# MIDIInterface.net
KiCad netlist of a schematic drawn in Altium Designer
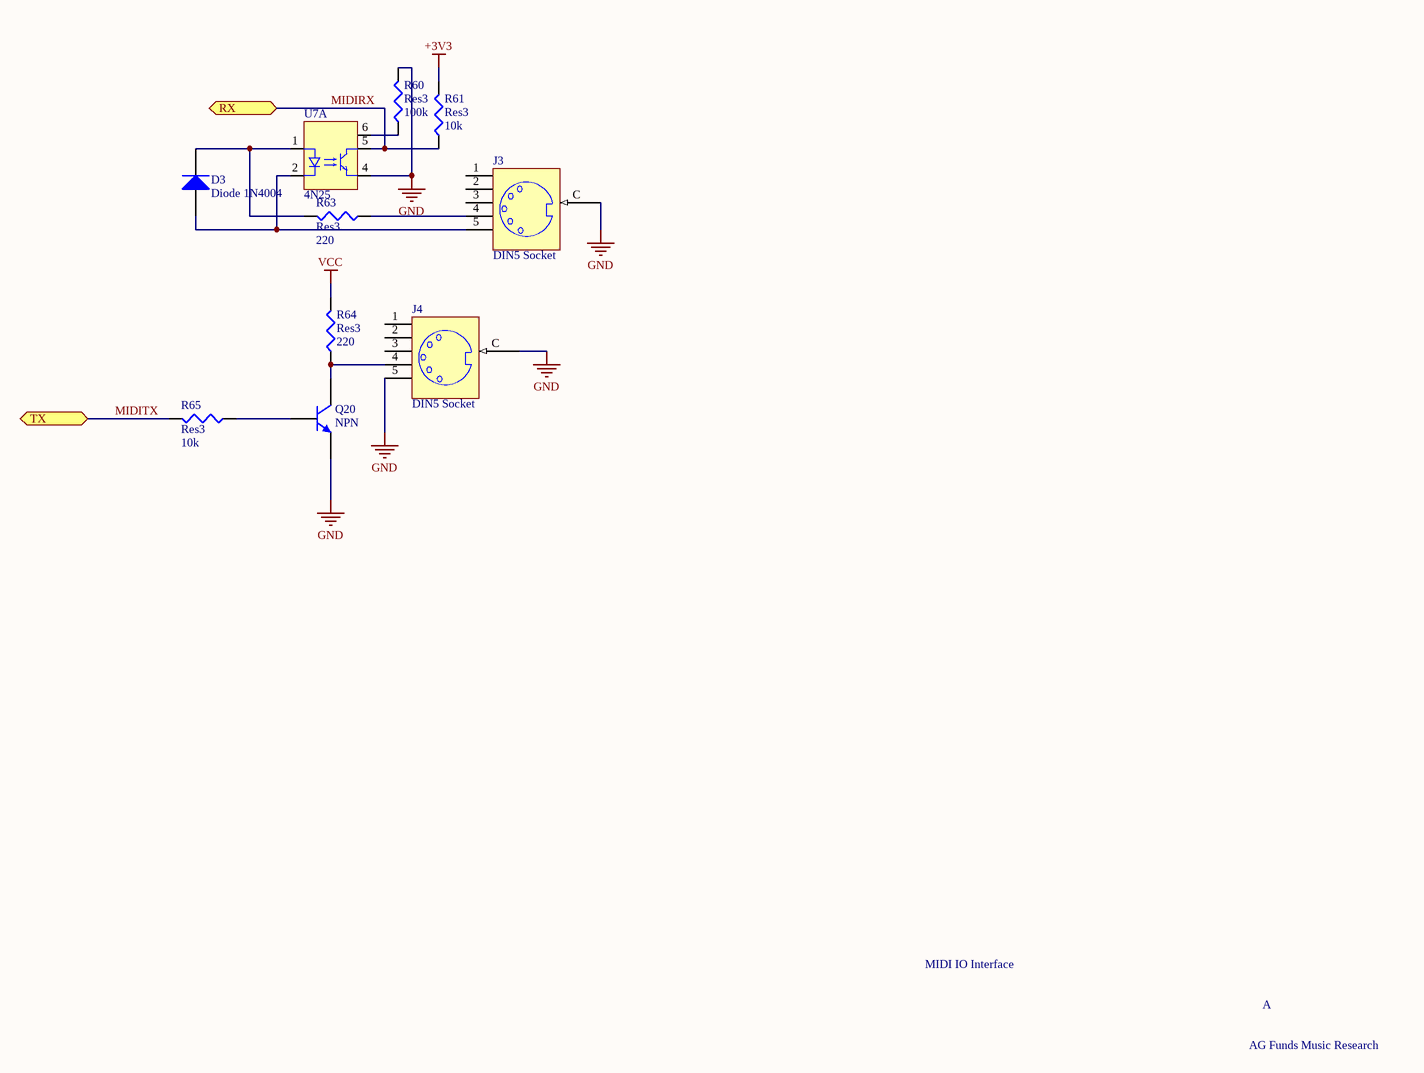
[diagram p0: MIDIInterface.SchDoc]

(export (version "E")
  (design (tool "Eeschema 10.0.6"))
  (components
    (comp (ref "D3")
      (value "Diode 1N4004")
      (footprint "DO-41")
      (description "1 Amp General Purpose Rectifier")
      (fields (field (name "PUBLISHER") "Altium Limited"))
      (libsource (lib "Miscellaneous Devices") (part "Diode 1N4004"))
    )
    (comp (ref "J3")
      (value "DIN5 Socket")
      (footprint "RGBLED:DIN-5")
      (description "CUI Inc. SDS-50J DIN5 PCB Mount Socket")
      (fields (field (name "PUBLISHER") "Altium Limited"))
      (libsource (lib "MIDIPiano_7") (part "DIN5"))
    )
    (comp (ref "J4")
      (value "DIN5 Socket")
      (footprint "RGBLED:DIN-5")
      (description "CUI Inc. SDS-50J DIN5 PCB Mount Socket")
      (fields (field (name "PUBLISHER") "Altium Limited"))
      (libsource (lib "MIDIPiano_7") (part "DIN5"))
    )
    (comp (ref "Q20")
      (value "NPN")
      (footprint "SOT95P230-3N")
      (description "BC817/BC818 SMD NPN Bipolar Transistor")
      (fields (field (name "PUBLISHER") "Altium Limited"))
      (libsource (lib "MIDIPiano_7") (part "NPN"))
    )
    (comp (ref "R60")
      (value "Res3")
      (footprint "J1-0603")
      (description "Resistor")
      (fields (field (name "ALTIUM_VALUE") "100k") (field (name "PUBLISHER") "Altium Limited"))
      (libsource (lib "Miscellaneous Devices") (part "Res3"))
    )
    (comp (ref "R61")
      (value "Res3")
      (footprint "J1-0603")
      (description "Resistor")
      (fields (field (name "ALTIUM_VALUE") "10k") (field (name "PUBLISHER") "Altium Limited"))
      (libsource (lib "Miscellaneous Devices") (part "Res3"))
    )
    (comp (ref "R63")
      (value "Res3")
      (footprint "J1-0603")
      (description "Resistor")
      (fields (field (name "ALTIUM_VALUE") "220") (field (name "PUBLISHER") "Altium Limited"))
      (libsource (lib "Miscellaneous Devices") (part "Res3"))
    )
    (comp (ref "R64")
      (value "Res3")
      (footprint "J1-0603")
      (description "Resistor")
      (fields (field (name "ALTIUM_VALUE") "220") (field (name "PUBLISHER") "Altium Limited"))
      (libsource (lib "Miscellaneous Devices") (part "Res3"))
    )
    (comp (ref "R65")
      (value "Res3")
      (footprint "J1-0603")
      (description "Resistor")
      (fields (field (name "ALTIUM_VALUE") "10k") (field (name "PUBLISHER") "Altium Limited"))
      (libsource (lib "Miscellaneous Devices") (part "Res3"))
    )
    (comp (ref "U7")
      (value "4N25")
      (footprint "DIP-6")
      (description "Optocoupler, Phototransistor Output, Dual Channel, TTL Compatible, Pb-free")
      (fields (field (name "PUBLISHER") "Altium Limited"))
      (libsource (lib "MIDIPiano_7") (part "4N25"))
    )
  )
  (nets
    (net (code "1") (name "+3V3") (class "Default")
      (node (ref "R61") (pin "2") (pinfunction "2_2") (pintype "passive"))
    )
    (net (code "2") (name "/MIDIRX") (class "Default")
      (node (ref "R61") (pin "1") (pinfunction "1_1") (pintype "passive"))
      (node (ref "U7") (pin "5") (pinfunction "C_5") (pintype "passive"))
    )
    (net (code "3") (name "/MIDITX") (class "Default")
      (node (ref "R65") (pin "2") (pinfunction "2_2") (pintype "passive"))
    )
    (net (code "4") (name "GND") (class "Default")
      (node (ref "J3") (pin "C") (pinfunction "C_C") (pintype "input"))
      (node (ref "J4") (pin "5") (pinfunction "5_5") (pintype "passive"))
      (node (ref "J4") (pin "C") (pinfunction "C_C") (pintype "input"))
      (node (ref "Q20") (pin "3") (pinfunction "E_3") (pintype "passive"))
      (node (ref "R60") (pin "2") (pinfunction "2_2") (pintype "passive"))
      (node (ref "U7") (pin "4") (pinfunction "E_4") (pintype "passive"))
    )
    (net (code "5") (name "Net-(D3-A)") (class "Default")
      (node (ref "D3") (pin "1") (pinfunction "A_1") (pintype "passive"))
      (node (ref "J3") (pin "5") (pinfunction "5_5") (pintype "passive"))
      (node (ref "U7") (pin "2") (pinfunction "K_2") (pintype "passive"))
    )
    (net (code "6") (name "Net-(D3-K)") (class "Default")
      (node (ref "D3") (pin "2") (pinfunction "K_2") (pintype "passive"))
      (node (ref "R63") (pin "2") (pinfunction "2_2") (pintype "passive"))
      (node (ref "U7") (pin "1") (pinfunction "A_1") (pintype "passive"))
    )
    (net (code "7") (name "Net-(J3-Pad4)") (class "Default")
      (node (ref "J3") (pin "4") (pinfunction "4_4") (pintype "passive"))
      (node (ref "R63") (pin "1") (pinfunction "1_1") (pintype "passive"))
    )
    (net (code "8") (name "Net-(Q20-B)") (class "Default")
      (node (ref "Q20") (pin "2") (pinfunction "B_2") (pintype "passive"))
      (node (ref "R65") (pin "1") (pinfunction "1_1") (pintype "passive"))
    )
    (net (code "9") (name "Net-(Q20-C)") (class "Default")
      (node (ref "J4") (pin "4") (pinfunction "4_4") (pintype "passive"))
      (node (ref "Q20") (pin "1") (pinfunction "C_1") (pintype "passive"))
      (node (ref "R64") (pin "1") (pinfunction "1_1") (pintype "passive"))
    )
    (net (code "10") (name "Net-(U7A-B)") (class "Default")
      (node (ref "R60") (pin "1") (pinfunction "1_1") (pintype "passive"))
      (node (ref "U7") (pin "6") (pinfunction "B_6") (pintype "passive"))
    )
    (net (code "11") (name "VCC") (class "Default")
      (node (ref "R64") (pin "2") (pinfunction "2_2") (pintype "passive"))
    )
    (net (code "12") (name "unconnected-(J3-Pad1)") (class "Default")
      (node (ref "J3") (pin "1") (pinfunction "1_1") (pintype "passive"))
    )
    (net (code "13") (name "unconnected-(J3-Pad2)") (class "Default")
      (node (ref "J3") (pin "2") (pinfunction "2_2") (pintype "passive"))
    )
    (net (code "14") (name "unconnected-(J3-Pad3)") (class "Default")
      (node (ref "J3") (pin "3") (pinfunction "3_3") (pintype "passive"))
    )
    (net (code "15") (name "unconnected-(J4-Pad1)") (class "Default")
      (node (ref "J4") (pin "1") (pinfunction "1_1") (pintype "passive"))
    )
    (net (code "16") (name "unconnected-(J4-Pad2)") (class "Default")
      (node (ref "J4") (pin "2") (pinfunction "2_2") (pintype "passive"))
    )
    (net (code "17") (name "unconnected-(J4-Pad3)") (class "Default")
      (node (ref "J4") (pin "3") (pinfunction "3_3") (pintype "passive"))
    )
  )
)
